# CircuitControlDriver.net
KiCad netlist of a schematic drawn in Altium Designer
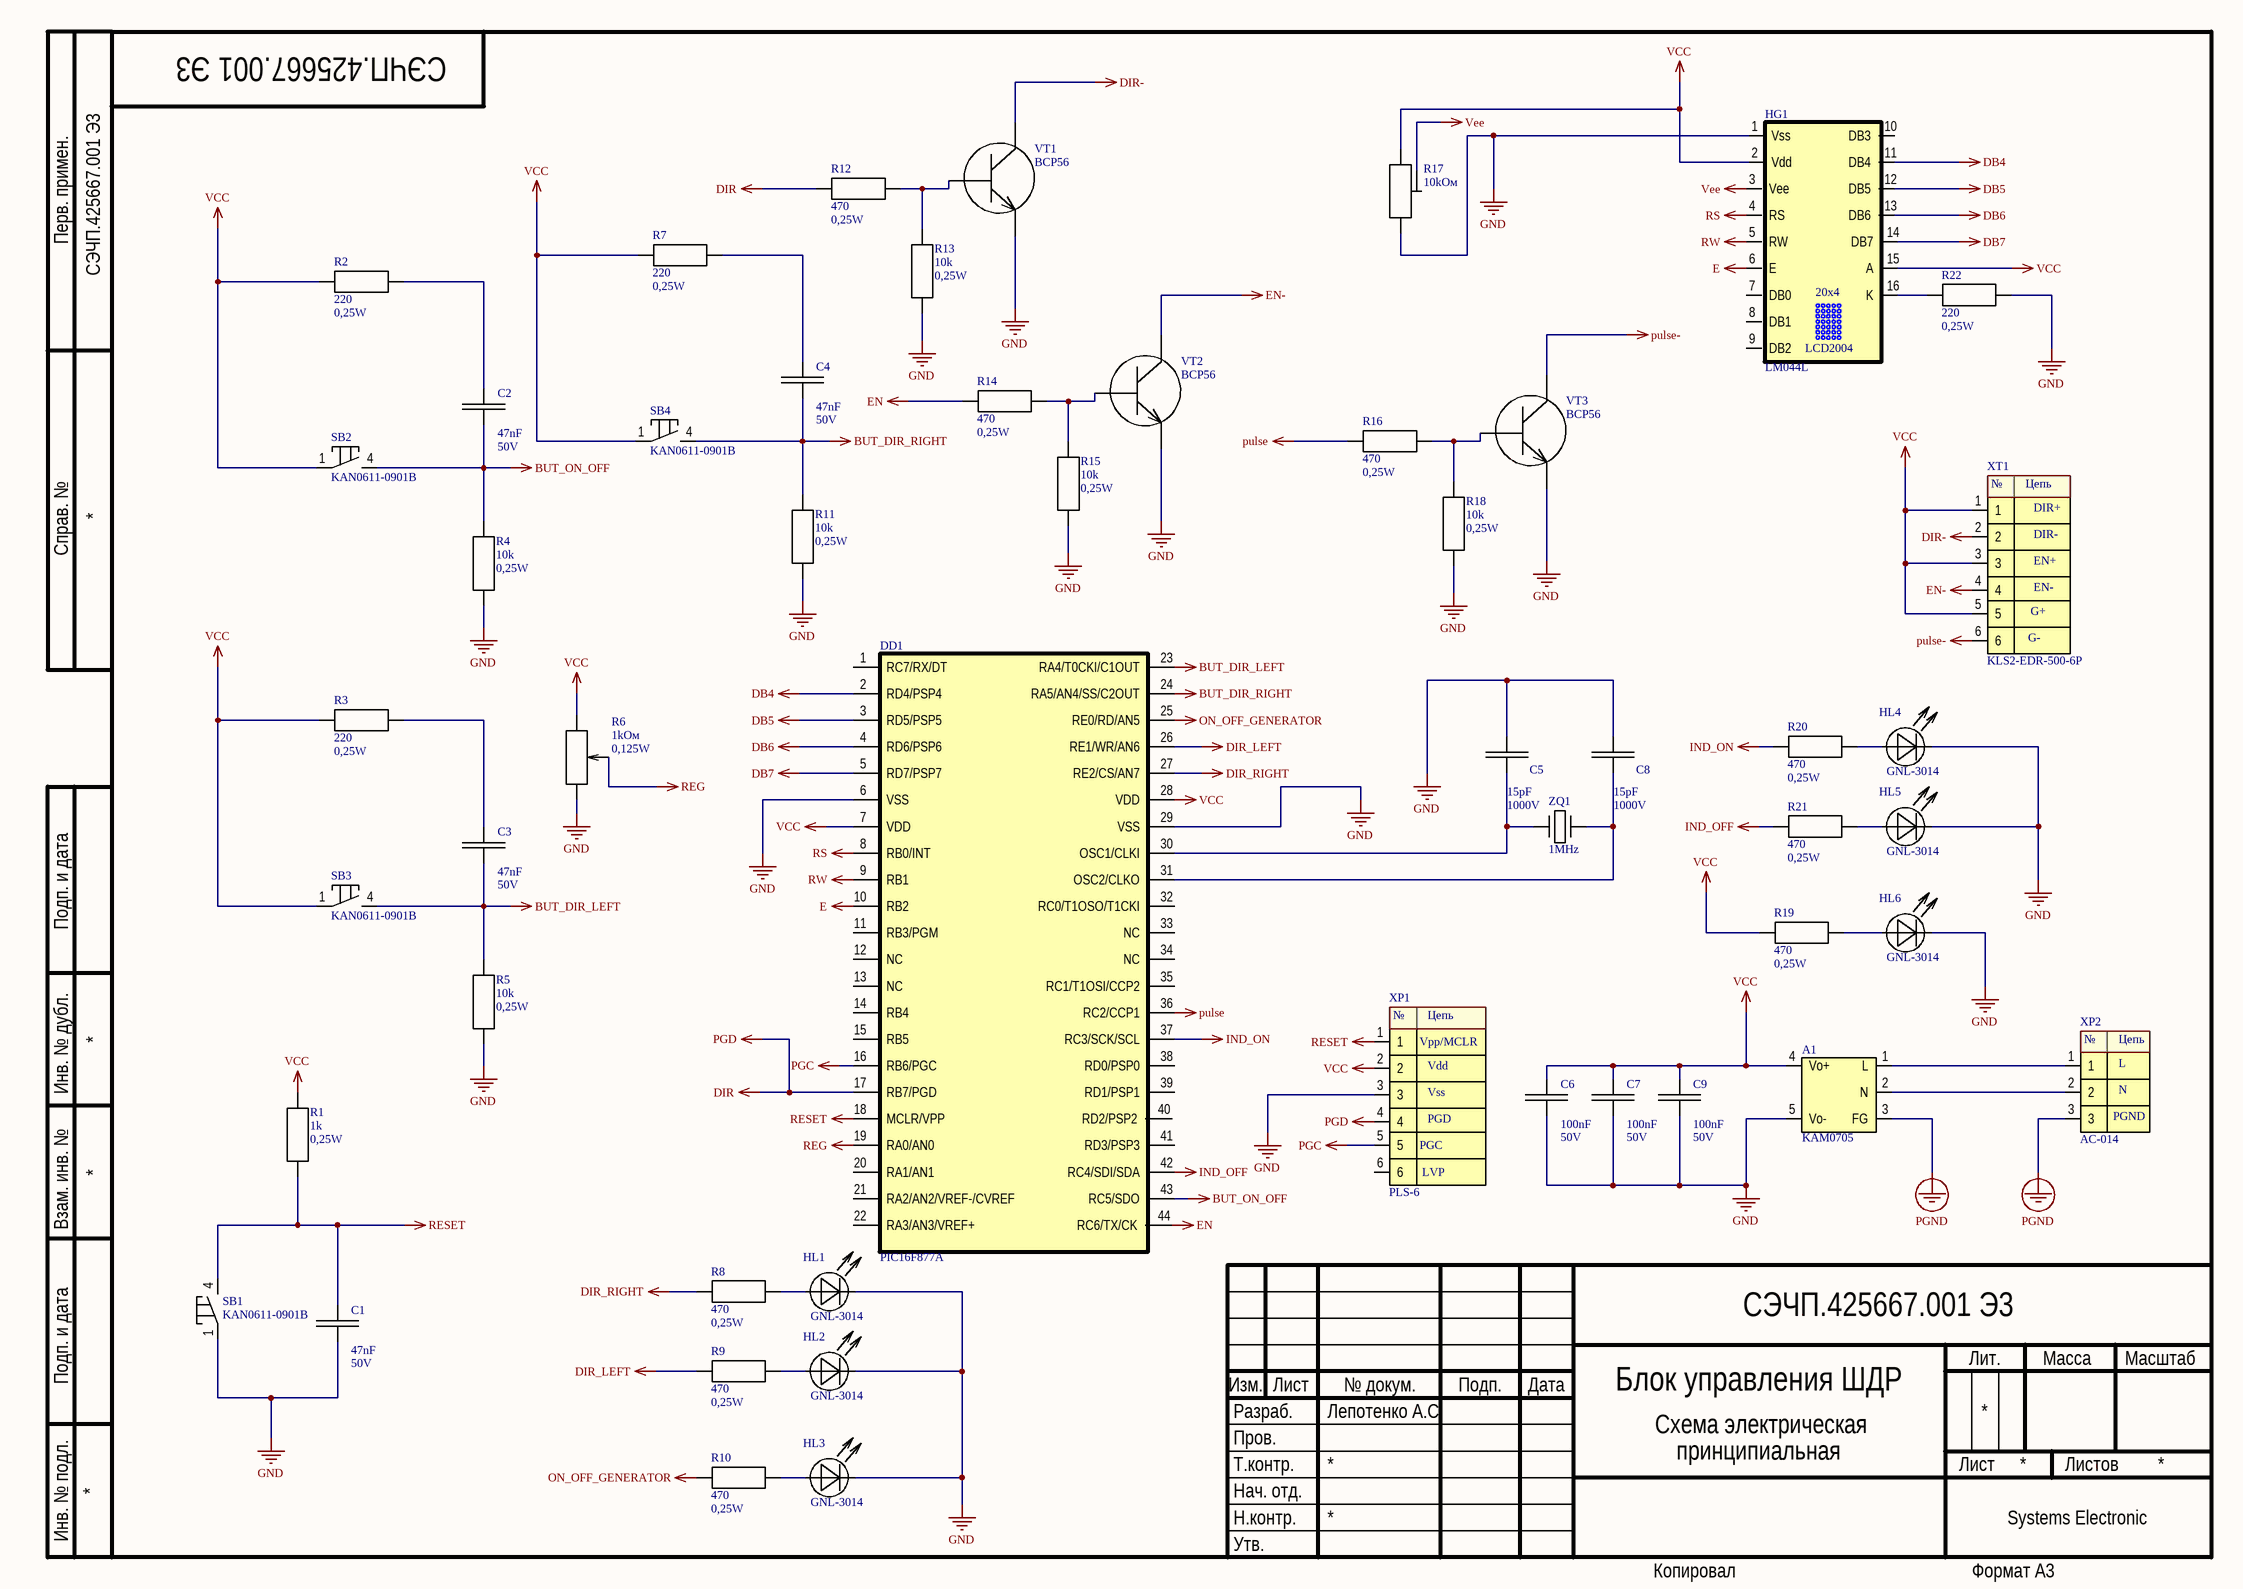
[diagram p0: CircuitControlDriver.SchDoc]

(export (version "E")
  (design (tool "Eeschema 10.0.6"))
  (components
    (comp (ref "A1")
      (value "KAM0705")
      (footprint "KAM705")
      (fields (field (name "MANUFACTURER") "CHINFA ELECTRONICS"))
      (libsource (lib "SchlibUGO") (part "KAM0705"))
    )
    (comp (ref "C1")
      (value "47nF")
      (footprint "CAP1206")
      (fields
        (field (name "VOLTAGE") "50V")
        (field (name "PART NUMBER") "120647nY5V-50V")
        (field (name "MANUFACTURER") "FAITHFULL LINK")
      )
      (libsource (lib "SchlibUGO") (part "Capasitor"))
    )
    (comp (ref "C2")
      (value "47nF")
      (footprint "CAP1206")
      (fields
        (field (name "VOLTAGE") "50V")
        (field (name "PART NUMBER") "120647nY5V-50V")
        (field (name "MANUFACTURER") "FAITHFULL LINK")
      )
      (libsource (lib "SchlibUGO") (part "Capasitor"))
    )
    (comp (ref "C3")
      (value "47nF")
      (footprint "CAP1206")
      (fields
        (field (name "VOLTAGE") "50V")
        (field (name "PART NUMBER") "120647nY5V-50V")
        (field (name "MANUFACTURER") "FAITHFULL LINK")
      )
      (libsource (lib "SchlibUGO") (part "Capasitor"))
    )
    (comp (ref "C4")
      (value "47nF")
      (footprint "CAP1206")
      (fields
        (field (name "VOLTAGE") "50V")
        (field (name "PART NUMBER") "120647nY5V-50V")
        (field (name "MANUFACTURER") "FAITHFULL LINK")
      )
      (libsource (lib "SchlibUGO") (part "Capasitor"))
    )
    (comp (ref "C5")
      (value "15pF")
      (footprint "CAP1206")
      (fields
        (field (name "VOLTAGE") "1000V")
        (field (name "PART NUMBER") "1206150NPO")
        (field (name "MANUFACTURER") "NPO")
      )
      (libsource (lib "SchlibUGO") (part "Capasitor"))
    )
    (comp (ref "C6")
      (value "100nF")
      (footprint "CAP1206")
      (fields
        (field (name "VOLTAGE") "50V")
        (field (name "PART NUMBER") "CL31B104KBCNNNC")
        (field (name "MANUFACTURER") "Samsung")
      )
      (libsource (lib "SchlibUGO") (part "Capasitor"))
    )
    (comp (ref "C7")
      (value "100nF")
      (footprint "CAP1206")
      (fields
        (field (name "VOLTAGE") "50V")
        (field (name "PART NUMBER") "CL31B104KBCNNNC")
        (field (name "MANUFACTURER") "Samsung")
      )
      (libsource (lib "SchlibUGO") (part "Capasitor"))
    )
    (comp (ref "C8")
      (value "15pF")
      (footprint "CAP1206")
      (fields
        (field (name "VOLTAGE") "1000V")
        (field (name "PART NUMBER") "1206150NPO")
        (field (name "MANUFACTURER") "NPO")
      )
      (libsource (lib "SchlibUGO") (part "Capasitor"))
    )
    (comp (ref "C9")
      (value "100nF")
      (footprint "CAP1206")
      (fields
        (field (name "VOLTAGE") "50V")
        (field (name "PART NUMBER") "CL31B104KBCNNNC")
        (field (name "MANUFACTURER") "Samsung")
      )
      (libsource (lib "SchlibUGO") (part "Capasitor"))
    )
    (comp (ref "DD1")
      (value "PIC16F877A")
      (footprint "TQFP80P1200X1200X120-44N")
      (fields (field (name "MANUFACTURER") "Micchip"))
      (libsource (lib "SchlibUGO") (part "PIC16F877A"))
    )
    (comp (ref "HG1")
      (value "LM044L")
      (footprint "LCD2004")
      (fields (field (name "PART NUMBER") "LM044L-HD44780U") (field (name "MANUFACTURER") "HITACHI"))
      (libsource (lib "SchlibUGO") (part "LM044L"))
    )
    (comp (ref "HL1")
      (value "GNL-3014")
      (footprint "GNL-3014")
      (fields (field (name "PART NUMBER") "GNL-3014SRD") (field (name "MANUFACTURER") "G-NOR"))
      (libsource (lib "SchlibUGO") (part "LED"))
    )
    (comp (ref "HL2")
      (value "GNL-3014")
      (footprint "GNL-3014")
      (fields (field (name "PART NUMBER") "GNL-3014SRD") (field (name "MANUFACTURER") "G-NOR"))
      (libsource (lib "SchlibUGO") (part "LED"))
    )
    (comp (ref "HL3")
      (value "GNL-3014")
      (footprint "GNL-3014")
      (fields (field (name "PART NUMBER") "GNL-3014SRD") (field (name "MANUFACTURER") "G-NOR"))
      (libsource (lib "SchlibUGO") (part "LED"))
    )
    (comp (ref "HL4")
      (value "GNL-3014")
      (footprint "GNL-3014")
      (fields (field (name "PART NUMBER") "GNL-3014SRD") (field (name "MANUFACTURER") "G-NOR"))
      (libsource (lib "SchlibUGO") (part "LED"))
    )
    (comp (ref "HL5")
      (value "GNL-3014")
      (footprint "GNL-3014")
      (fields (field (name "PART NUMBER") "GNL-3014SRD") (field (name "MANUFACTURER") "G-NOR"))
      (libsource (lib "SchlibUGO") (part "LED"))
    )
    (comp (ref "HL6")
      (value "GNL-3014")
      (footprint "GNL-3014")
      (fields (field (name "PART NUMBER") "GNL-3014SRD") (field (name "MANUFACTURER") "G-NOR"))
      (libsource (lib "SchlibUGO") (part "LED"))
    )
    (comp (ref "R1")
      (value "1k")
      (footprint "1206")
      (fields
        (field (name "MANUFACTURER") "Royal Ohm")
        (field (name "PART NUMBER") "RC1206FR-071KL")
        (field (name "POWER") "0,25W")
        (field (name "Comment") "10k")
      )
      (libsource (lib "SchlibUGO") (part "Resistor"))
    )
    (comp (ref "R2")
      (value "220")
      (footprint "1206")
      (fields
        (field (name "MANUFACTURER") "YAGEO")
        (field (name "PART NUMBER") "RC1206JR-07220L")
        (field (name "POWER") "0,25W")
      )
      (libsource (lib "SchlibUGO") (part "Resistor"))
    )
    (comp (ref "R3")
      (value "220")
      (footprint "1206")
      (fields
        (field (name "MANUFACTURER") "YAGEO")
        (field (name "PART NUMBER") "RC1206JR-07220L")
        (field (name "POWER") "0,25W")
      )
      (libsource (lib "SchlibUGO") (part "Resistor"))
    )
    (comp (ref "R4")
      (value "10k")
      (footprint "1206")
      (fields
        (field (name "MANUFACTURER") "YAGEO")
        (field (name "PART NUMBER") "RC1206JR-0710KL")
        (field (name "POWER") "0,25W")
      )
      (libsource (lib "SchlibUGO") (part "Resistor"))
    )
    (comp (ref "R5")
      (value "10k")
      (footprint "1206")
      (fields
        (field (name "MANUFACTURER") "YAGEO")
        (field (name "PART NUMBER") "RC1206JR-0710KL")
        (field (name "POWER") "0,25W")
      )
      (libsource (lib "SchlibUGO") (part "Resistor"))
    )
    (comp (ref "R6")
      (value "1kОм")
      (footprint "KC/C 16K1")
      (fields
        (field (name "PART NUMBER") "16K1")
        (field (name "MANUFACTURER") "RUICHI")
        (field (name "POWER") "0,125W")
      )
      (libsource (lib "SchlibUGO") (part "POT-HG"))
    )
    (comp (ref "R7")
      (value "220")
      (footprint "1206")
      (fields
        (field (name "MANUFACTURER") "YAGEO")
        (field (name "PART NUMBER") "RC1206JR-07220L")
        (field (name "POWER") "0,25W")
      )
      (libsource (lib "SchlibUGO") (part "Resistor"))
    )
    (comp (ref "R8")
      (value "470")
      (footprint "1206")
      (fields
        (field (name "MANUFACTURER") "YAGEO")
        (field (name "PART NUMBER") "RC1206JR-07470RL")
        (field (name "POWER") "0,25W")
      )
      (libsource (lib "SchlibUGO") (part "Resistor"))
    )
    (comp (ref "R9")
      (value "470")
      (footprint "1206")
      (fields
        (field (name "MANUFACTURER") "YAGEO")
        (field (name "PART NUMBER") "RC1206JR-07470RL")
        (field (name "POWER") "0,25W")
      )
      (libsource (lib "SchlibUGO") (part "Resistor"))
    )
    (comp (ref "R10")
      (value "470")
      (footprint "1206")
      (fields
        (field (name "MANUFACTURER") "YAGEO")
        (field (name "PART NUMBER") "RC1206JR-07470RL")
        (field (name "POWER") "0,25W")
      )
      (libsource (lib "SchlibUGO") (part "Resistor"))
    )
    (comp (ref "R11")
      (value "10k")
      (footprint "1206")
      (fields
        (field (name "MANUFACTURER") "YAGEO")
        (field (name "PART NUMBER") "RC1206JR-0710KL")
        (field (name "POWER") "0,25W")
      )
      (libsource (lib "SchlibUGO") (part "Resistor"))
    )
    (comp (ref "R12")
      (value "470")
      (footprint "1206")
      (fields
        (field (name "MANUFACTURER") "YAGEO")
        (field (name "PART NUMBER") "RC1206JR-07470RL")
        (field (name "POWER") "0,25W")
      )
      (libsource (lib "SchlibUGO") (part "Resistor"))
    )
    (comp (ref "R13")
      (value "10k")
      (footprint "1206")
      (fields
        (field (name "MANUFACTURER") "YAGEO")
        (field (name "PART NUMBER") "RC1206JR-0710KL")
        (field (name "POWER") "0,25W")
      )
      (libsource (lib "SchlibUGO") (part "Resistor"))
    )
    (comp (ref "R14")
      (value "470")
      (footprint "1206")
      (fields
        (field (name "MANUFACTURER") "YAGEO")
        (field (name "PART NUMBER") "RC1206JR-07470RL")
        (field (name "POWER") "0,25W")
      )
      (libsource (lib "SchlibUGO") (part "Resistor"))
    )
    (comp (ref "R15")
      (value "10k")
      (footprint "1206")
      (fields
        (field (name "MANUFACTURER") "YAGEO")
        (field (name "PART NUMBER") "RC1206JR-0710KL")
        (field (name "POWER") "0,25W")
      )
      (libsource (lib "SchlibUGO") (part "Resistor"))
    )
    (comp (ref "R16")
      (value "470")
      (footprint "1206")
      (fields
        (field (name "MANUFACTURER") "YAGEO")
        (field (name "PART NUMBER") "RC1206JR-07470RL")
        (field (name "POWER") "0,25W")
      )
      (libsource (lib "SchlibUGO") (part "Resistor"))
    )
    (comp (ref "R17")
      (value "10kОм")
      (footprint "3006P")
      (fields
        (field (name "PART NUMBER") "3006-103-Z-LF")
        (field (name "MANUFACTURER") "Bours")
        (field (name "POWER") "0,125W")
      )
      (libsource (lib "SchlibUGO") (part "POT"))
    )
    (comp (ref "R18")
      (value "10k")
      (footprint "1206")
      (fields
        (field (name "MANUFACTURER") "YAGEO")
        (field (name "PART NUMBER") "RC1206JR-0710KL")
        (field (name "POWER") "0,25W")
      )
      (libsource (lib "SchlibUGO") (part "Resistor"))
    )
    (comp (ref "R19")
      (value "470")
      (footprint "1206")
      (fields
        (field (name "MANUFACTURER") "YAGEO")
        (field (name "PART NUMBER") "RC1206JR-07470RL")
        (field (name "POWER") "0,25W")
      )
      (libsource (lib "SchlibUGO") (part "Resistor"))
    )
    (comp (ref "R20")
      (value "470")
      (footprint "1206")
      (fields
        (field (name "MANUFACTURER") "YAGEO")
        (field (name "PART NUMBER") "RC1206JR-07470RL")
        (field (name "POWER") "0,25W")
      )
      (libsource (lib "SchlibUGO") (part "Resistor"))
    )
    (comp (ref "R21")
      (value "470")
      (footprint "1206")
      (fields
        (field (name "MANUFACTURER") "YAGEO")
        (field (name "PART NUMBER") "RC1206JR-07470RL")
        (field (name "POWER") "0,25W")
      )
      (libsource (lib "SchlibUGO") (part "Resistor"))
    )
    (comp (ref "R22")
      (value "220")
      (footprint "1206")
      (fields
        (field (name "MANUFACTURER") "YAGEO")
        (field (name "PART NUMBER") "RC1206JR-07220L")
        (field (name "POWER") "0,25W")
      )
      (libsource (lib "SchlibUGO") (part "Resistor"))
    )
    (comp (ref "SB1")
      (value "KAN0611-0901B")
      (footprint "KLS2")
      (fields (field (name "MANUFACTURER") "RUICHI"))
      (libsource (lib "SchlibUGO") (part "Button"))
    )
    (comp (ref "SB2")
      (value "KAN0611-0901B")
      (footprint "KLS2")
      (fields (field (name "MANUFACTURER") "RUICHI"))
      (libsource (lib "SchlibUGO") (part "Button"))
    )
    (comp (ref "SB3")
      (value "KAN0611-0901B")
      (footprint "KLS2")
      (fields (field (name "MANUFACTURER") "RUICHI"))
      (libsource (lib "SchlibUGO") (part "Button"))
    )
    (comp (ref "SB4")
      (value "KAN0611-0901B")
      (footprint "KLS2")
      (fields (field (name "MANUFACTURER") "RUICHI"))
      (libsource (lib "SchlibUGO") (part "Button"))
    )
    (comp (ref "VT1")
      (value "BCP56")
      (footprint "SOT223")
      (fields (field (name "PART NUMBER") "BCP56-16") (field (name "MANUFACTURER") "NXP Semiconductors"))
      (libsource (lib "SchlibUGO") (part "BCP56-16"))
    )
    (comp (ref "VT2")
      (value "BCP56")
      (footprint "SOT223")
      (fields (field (name "PART NUMBER") "BCP56-16") (field (name "MANUFACTURER") "NXP Semiconductors"))
      (libsource (lib "SchlibUGO") (part "BCP56-16"))
    )
    (comp (ref "VT3")
      (value "BCP56")
      (footprint "SOT223")
      (fields (field (name "PART NUMBER") "BCP56-16") (field (name "MANUFACTURER") "NXP Semiconductors"))
      (libsource (lib "SchlibUGO") (part "BCP56-16"))
    )
    (comp (ref "XP1")
      (value "PLS-6")
      (footprint "DS1021-6")
      (fields (field (name "PART NUMBER") "PLS-40") (field (name "MANUFACTURER") "RUICHI"))
      (libsource (lib "SchlibUGO") (part "PLS-6-1"))
    )
    (comp (ref "XP2")
      (value "AC-014")
      (footprint "Power AC-014")
      (fields (field (name "MANUFACTURER") "RUICHI"))
      (libsource (lib "SchlibUGO") (part "Power Connector AC-014"))
    )
    (comp (ref "XT1")
      (value "KLS2-EDR-500-6P")
      (footprint "KLS2-EDR-500-6P")
      (fields (field (name "MANUFACTURER") "KLS"))
      (libsource (lib "SchlibUGO") (part "KLS2-EDR-500-6P"))
    )
    (comp (ref "ZQ1")
      (value "1MHz")
      (footprint "HC-51U")
      (fields (field (name "PART NUMBER") "HC-51") (field (name "MANUFACTURER") "CHina"))
      (libsource (lib "SchlibUGO") (part "Rzanator"))
    )
  )
  (nets
    (net (code "1") (name "BUT_DIR_LEFT") (class "Default")
      (node (ref "C3") (pin "2") (pinfunction "2_2") (pintype "passive"))
      (node (ref "DD1") (pin "23") (pinfunction "RA4/T0CKI/C1OUT_23") (pintype "passive"))
      (node (ref "R5") (pin "1") (pinfunction "1_1") (pintype "passive"))
      (node (ref "SB3") (pin "4") (pinfunction "4_4") (pintype "passive"))
    )
    (net (code "2") (name "BUT_DIR_RIGHT") (class "Default")
      (node (ref "C4") (pin "2") (pinfunction "2_2") (pintype "passive"))
      (node (ref "DD1") (pin "24") (pinfunction "RA5/AN4/SS/C2OUT_24") (pintype "passive"))
      (node (ref "R11") (pin "1") (pinfunction "1_1") (pintype "passive"))
      (node (ref "SB4") (pin "4") (pinfunction "4_4") (pintype "passive"))
    )
    (net (code "3") (name "BUT_ON_OFF") (class "Default")
      (node (ref "C2") (pin "2") (pinfunction "2_2") (pintype "passive"))
      (node (ref "DD1") (pin "43") (pinfunction "RC5/SDO_43") (pintype "passive"))
      (node (ref "R4") (pin "1") (pinfunction "1_1") (pintype "passive"))
      (node (ref "SB2") (pin "4") (pinfunction "4_4") (pintype "passive"))
    )
    (net (code "4") (name "DB4") (class "Default")
      (node (ref "DD1") (pin "2") (pinfunction "RD4/PSP4_2") (pintype "passive"))
      (node (ref "HG1") (pin "11") (pinfunction "DB4_11") (pintype "passive"))
    )
    (net (code "5") (name "DB5") (class "Default")
      (node (ref "DD1") (pin "3") (pinfunction "RD5/PSP5_3") (pintype "passive"))
      (node (ref "HG1") (pin "12") (pinfunction "DB5_12") (pintype "passive"))
    )
    (net (code "6") (name "DB6") (class "Default")
      (node (ref "DD1") (pin "4") (pinfunction "RD6/PSP6_4") (pintype "passive"))
      (node (ref "HG1") (pin "13") (pinfunction "DB6_13") (pintype "passive"))
    )
    (net (code "7") (name "DB7") (class "Default")
      (node (ref "DD1") (pin "5") (pinfunction "RD7/PSP7_5") (pintype "passive"))
      (node (ref "HG1") (pin "14") (pinfunction "DB7_14") (pintype "passive"))
    )
    (net (code "8") (name "DIR") (class "Default")
      (node (ref "DD1") (pin "17") (pinfunction "RB7/PGD_17") (pintype "passive"))
      (node (ref "R12") (pin "1") (pinfunction "1_1") (pintype "passive"))
      (node (ref "XP1") (pin "4") (pinfunction "4_4") (pintype "passive"))
    )
    (net (code "9") (name "DIR-") (class "Default")
      (node (ref "VT1") (pin "2") (pinfunction "2_2") (pintype "passive"))
      (node (ref "XT1") (pin "2") (pinfunction "2_2") (pintype "passive"))
    )
    (net (code "10") (name "DIR_LEFT") (class "Default")
      (node (ref "DD1") (pin "26") (pinfunction "RE1/WR/AN6_26") (pintype "passive"))
      (node (ref "R9") (pin "1") (pinfunction "1_1") (pintype "passive"))
    )
    (net (code "11") (name "DIR_RIGHT") (class "Default")
      (node (ref "DD1") (pin "27") (pinfunction "RE2/CS/AN7_27") (pintype "passive"))
      (node (ref "R8") (pin "1") (pinfunction "1_1") (pintype "passive"))
    )
    (net (code "12") (name "E") (class "Default")
      (node (ref "DD1") (pin "10") (pinfunction "RB2_10") (pintype "passive"))
      (node (ref "HG1") (pin "6") (pinfunction "E_6") (pintype "passive"))
    )
    (net (code "13") (name "EN") (class "Default")
      (node (ref "DD1") (pin "44") (pinfunction "RC6/TX/CK_44") (pintype "passive"))
      (node (ref "R14") (pin "1") (pinfunction "1_1") (pintype "passive"))
    )
    (net (code "14") (name "EN-") (class "Default")
      (node (ref "VT2") (pin "2") (pinfunction "2_2") (pintype "passive"))
      (node (ref "XT1") (pin "4") (pinfunction "4_4") (pintype "passive"))
    )
    (net (code "15") (name "GND") (class "Default")
      (node (ref "A1") (pin "5") (pinfunction "Vo-_5") (pintype "passive"))
      (node (ref "C1") (pin "2") (pinfunction "2_2") (pintype "passive"))
      (node (ref "C5") (pin "1") (pinfunction "1_1") (pintype "passive"))
      (node (ref "C6") (pin "2") (pinfunction "2_2") (pintype "passive"))
      (node (ref "C7") (pin "2") (pinfunction "2_2") (pintype "passive"))
      (node (ref "C8") (pin "1") (pinfunction "1_1") (pintype "passive"))
      (node (ref "C9") (pin "2") (pinfunction "2_2") (pintype "passive"))
      (node (ref "DD1") (pin "29") (pinfunction "VSS_29") (pintype "passive"))
      (node (ref "DD1") (pin "6") (pinfunction "VSS_6") (pintype "passive"))
      (node (ref "HG1") (pin "1") (pinfunction "Vss_1") (pintype "passive"))
      (node (ref "HL1") (pin "2") (pinfunction "2_2") (pintype "passive"))
      (node (ref "HL2") (pin "2") (pinfunction "2_2") (pintype "passive"))
      (node (ref "HL3") (pin "2") (pinfunction "2_2") (pintype "passive"))
      (node (ref "HL4") (pin "2") (pinfunction "2_2") (pintype "passive"))
      (node (ref "HL5") (pin "2") (pinfunction "2_2") (pintype "passive"))
      (node (ref "HL6") (pin "2") (pinfunction "2_2") (pintype "passive"))
      (node (ref "R11") (pin "2") (pinfunction "2_2") (pintype "passive"))
      (node (ref "R13") (pin "2") (pinfunction "2_2") (pintype "passive"))
      (node (ref "R15") (pin "2") (pinfunction "2_2") (pintype "passive"))
      (node (ref "R17") (pin "1") (pinfunction "1_1") (pintype "passive"))
      (node (ref "R18") (pin "2") (pinfunction "2_2") (pintype "passive"))
      (node (ref "R22") (pin "1") (pinfunction "1_1") (pintype "passive"))
      (node (ref "R4") (pin "2") (pinfunction "2_2") (pintype "passive"))
      (node (ref "R5") (pin "2") (pinfunction "2_2") (pintype "passive"))
      (node (ref "R6") (pin "3") (pinfunction "3_3") (pintype "passive"))
      (node (ref "SB1") (pin "1") (pinfunction "1_1") (pintype "passive"))
      (node (ref "VT1") (pin "3") (pinfunction "3_3") (pintype "passive"))
      (node (ref "VT2") (pin "3") (pinfunction "3_3") (pintype "passive"))
      (node (ref "VT3") (pin "3") (pinfunction "3_3") (pintype "passive"))
      (node (ref "XP1") (pin "3") (pinfunction "3_3") (pintype "passive"))
    )
    (net (code "16") (name "IND_OFF") (class "Default")
      (node (ref "DD1") (pin "42") (pinfunction "RC4/SDI/SDA_42") (pintype "passive"))
      (node (ref "R21") (pin "1") (pinfunction "1_1") (pintype "passive"))
    )
    (net (code "17") (name "IND_ON") (class "Default")
      (node (ref "DD1") (pin "37") (pinfunction "RC3/SCK/SCL_37") (pintype "passive"))
      (node (ref "R20") (pin "1") (pinfunction "1_1") (pintype "passive"))
    )
    (net (code "18") (name "Net-(A1-L)") (class "Default")
      (node (ref "A1") (pin "1") (pinfunction "L_1") (pintype "passive"))
      (node (ref "XP2") (pin "1") (pinfunction "1_1") (pintype "passive"))
    )
    (net (code "19") (name "Net-(A1-N)") (class "Default")
      (node (ref "A1") (pin "2") (pinfunction "N_2") (pintype "passive"))
      (node (ref "XP2") (pin "2") (pinfunction "2_2") (pintype "passive"))
    )
    (net (code "20") (name "Net-(C2-Pad1)") (class "Default")
      (node (ref "C2") (pin "1") (pinfunction "1_1") (pintype "passive"))
      (node (ref "R2") (pin "1") (pinfunction "1_1") (pintype "passive"))
    )
    (net (code "21") (name "Net-(C3-Pad1)") (class "Default")
      (node (ref "C3") (pin "1") (pinfunction "1_1") (pintype "passive"))
      (node (ref "R3") (pin "1") (pinfunction "1_1") (pintype "passive"))
    )
    (net (code "22") (name "Net-(C4-Pad1)") (class "Default")
      (node (ref "C4") (pin "1") (pinfunction "1_1") (pintype "passive"))
      (node (ref "R7") (pin "1") (pinfunction "1_1") (pintype "passive"))
    )
    (net (code "23") (name "Net-(DD1-OSC1{slash}CLKI)") (class "Default")
      (node (ref "C5") (pin "2") (pinfunction "2_2") (pintype "passive"))
      (node (ref "DD1") (pin "30") (pinfunction "OSC1/CLKI_30") (pintype "passive"))
      (node (ref "ZQ1") (pin "1") (pinfunction "1_1") (pintype "passive"))
    )
    (net (code "24") (name "Net-(DD1-OSC2{slash}CLKO)") (class "Default")
      (node (ref "C8") (pin "2") (pinfunction "2_2") (pintype "passive"))
      (node (ref "DD1") (pin "31") (pinfunction "OSC2/CLKO_31") (pintype "passive"))
      (node (ref "ZQ1") (pin "2") (pinfunction "2_2") (pintype "passive"))
    )
    (net (code "25") (name "Net-(HG1-K)") (class "Default")
      (node (ref "HG1") (pin "16") (pinfunction "K_16") (pintype "passive"))
      (node (ref "R22") (pin "2") (pinfunction "2_2") (pintype "passive"))
    )
    (net (code "26") (name "Net-(HL1-Pad1)") (class "Default")
      (node (ref "HL1") (pin "1") (pinfunction "1_1") (pintype "passive"))
      (node (ref "R8") (pin "2") (pinfunction "2_2") (pintype "passive"))
    )
    (net (code "27") (name "Net-(HL2-Pad1)") (class "Default")
      (node (ref "HL2") (pin "1") (pinfunction "1_1") (pintype "passive"))
      (node (ref "R9") (pin "2") (pinfunction "2_2") (pintype "passive"))
    )
    (net (code "28") (name "Net-(HL3-Pad1)") (class "Default")
      (node (ref "HL3") (pin "1") (pinfunction "1_1") (pintype "passive"))
      (node (ref "R10") (pin "2") (pinfunction "2_2") (pintype "passive"))
    )
    (net (code "29") (name "Net-(HL4-Pad1)") (class "Default")
      (node (ref "HL4") (pin "1") (pinfunction "1_1") (pintype "passive"))
      (node (ref "R20") (pin "2") (pinfunction "2_2") (pintype "passive"))
    )
    (net (code "30") (name "Net-(HL5-Pad1)") (class "Default")
      (node (ref "HL5") (pin "1") (pinfunction "1_1") (pintype "passive"))
      (node (ref "R21") (pin "2") (pinfunction "2_2") (pintype "passive"))
    )
    (net (code "31") (name "Net-(HL6-Pad1)") (class "Default")
      (node (ref "HL6") (pin "1") (pinfunction "1_1") (pintype "passive"))
      (node (ref "R19") (pin "2") (pinfunction "2_2") (pintype "passive"))
    )
    (net (code "32") (name "Net-(R12-Pad2)") (class "Default")
      (node (ref "R12") (pin "2") (pinfunction "2_2") (pintype "passive"))
      (node (ref "R13") (pin "1") (pinfunction "1_1") (pintype "passive"))
      (node (ref "VT1") (pin "1") (pinfunction "1_1") (pintype "passive"))
    )
    (net (code "33") (name "Net-(R14-Pad2)") (class "Default")
      (node (ref "R14") (pin "2") (pinfunction "2_2") (pintype "passive"))
      (node (ref "R15") (pin "1") (pinfunction "1_1") (pintype "passive"))
      (node (ref "VT2") (pin "1") (pinfunction "1_1") (pintype "passive"))
    )
    (net (code "34") (name "Net-(R16-Pad2)") (class "Default")
      (node (ref "R16") (pin "2") (pinfunction "2_2") (pintype "passive"))
      (node (ref "R18") (pin "1") (pinfunction "1_1") (pintype "passive"))
      (node (ref "VT3") (pin "1") (pinfunction "1_1") (pintype "passive"))
    )
    (net (code "35") (name "ON_OFF_GENERATOR") (class "Default")
      (node (ref "DD1") (pin "25") (pinfunction "RE0/RD/AN5_25") (pintype "passive"))
      (node (ref "R10") (pin "1") (pinfunction "1_1") (pintype "passive"))
    )
    (net (code "36") (name "PGC") (class "Default")
      (node (ref "DD1") (pin "16") (pinfunction "RB6/PGC_16") (pintype "passive"))
      (node (ref "XP1") (pin "5") (pinfunction "5_5") (pintype "passive"))
    )
    (net (code "37") (name "PGND") (class "Default")
      (node (ref "A1") (pin "3") (pinfunction "FG_3") (pintype "passive"))
      (node (ref "XP2") (pin "3") (pinfunction "3_3") (pintype "passive"))
    )
    (net (code "38") (name "REG") (class "Default")
      (node (ref "DD1") (pin "19") (pinfunction "RA0/AN0_19") (pintype "passive"))
      (node (ref "R6") (pin "2") (pinfunction "2_2") (pintype "passive"))
    )
    (net (code "39") (name "RESET") (class "Default")
      (node (ref "C1") (pin "1") (pinfunction "1_1") (pintype "passive"))
      (node (ref "DD1") (pin "18") (pinfunction "MCLR/VPP_18") (pintype "passive"))
      (node (ref "R1") (pin "2") (pinfunction "2_2") (pintype "passive"))
      (node (ref "SB1") (pin "4") (pinfunction "4_4") (pintype "passive"))
      (node (ref "XP1") (pin "1") (pinfunction "1_1") (pintype "passive"))
    )
    (net (code "40") (name "RS") (class "Default")
      (node (ref "DD1") (pin "8") (pinfunction "RB0/INT_8") (pintype "passive"))
      (node (ref "HG1") (pin "4") (pinfunction "RS_4") (pintype "passive"))
    )
    (net (code "41") (name "RW") (class "Default")
      (node (ref "DD1") (pin "9") (pinfunction "RB1_9") (pintype "passive"))
      (node (ref "HG1") (pin "5") (pinfunction "RW_5") (pintype "passive"))
    )
    (net (code "42") (name "VCC") (class "Default")
      (node (ref "A1") (pin "4") (pinfunction "Vo+_4") (pintype "passive"))
      (node (ref "C6") (pin "1") (pinfunction "1_1") (pintype "passive"))
      (node (ref "C7") (pin "1") (pinfunction "1_1") (pintype "passive"))
      (node (ref "C9") (pin "1") (pinfunction "1_1") (pintype "passive"))
      (node (ref "DD1") (pin "28") (pinfunction "VDD_28") (pintype "passive"))
      (node (ref "DD1") (pin "7") (pinfunction "VDD_7") (pintype "passive"))
      (node (ref "HG1") (pin "15") (pinfunction "A_15") (pintype "passive"))
      (node (ref "HG1") (pin "2") (pinfunction "Vdd_2") (pintype "passive"))
      (node (ref "R1") (pin "1") (pinfunction "1_1") (pintype "passive"))
      (node (ref "R17") (pin "3") (pinfunction "3_3") (pintype "passive"))
      (node (ref "R19") (pin "1") (pinfunction "1_1") (pintype "passive"))
      (node (ref "R2") (pin "2") (pinfunction "2_2") (pintype "passive"))
      (node (ref "R3") (pin "2") (pinfunction "2_2") (pintype "passive"))
      (node (ref "R6") (pin "1") (pinfunction "1_1") (pintype "passive"))
      (node (ref "R7") (pin "2") (pinfunction "2_2") (pintype "passive"))
      (node (ref "SB2") (pin "1") (pinfunction "1_1") (pintype "passive"))
      (node (ref "SB3") (pin "1") (pinfunction "1_1") (pintype "passive"))
      (node (ref "SB4") (pin "1") (pinfunction "1_1") (pintype "passive"))
      (node (ref "XP1") (pin "2") (pinfunction "2_2") (pintype "passive"))
      (node (ref "XT1") (pin "1") (pinfunction "1_1") (pintype "passive"))
      (node (ref "XT1") (pin "3") (pinfunction "3_3") (pintype "passive"))
      (node (ref "XT1") (pin "5") (pinfunction "5_5") (pintype "passive"))
    )
    (net (code "43") (name "Vee") (class "Default")
      (node (ref "HG1") (pin "3") (pinfunction "Vee_3") (pintype "passive"))
      (node (ref "R17") (pin "2") (pinfunction "2_2") (pintype "passive"))
    )
    (net (code "44") (name "pulse") (class "Default")
      (node (ref "DD1") (pin "36") (pinfunction "RC2/CCP1_36") (pintype "passive"))
      (node (ref "R16") (pin "1") (pinfunction "1_1") (pintype "passive"))
    )
    (net (code "45") (name "pulse-") (class "Default")
      (node (ref "VT3") (pin "2") (pinfunction "2_2") (pintype "passive"))
      (node (ref "XT1") (pin "6") (pinfunction "6_6") (pintype "passive"))
    )
    (net (code "46") (name "unconnected-(DD1-NC-Pad12)") (class "Default")
      (node (ref "DD1") (pin "12") (pinfunction "NC_12") (pintype "passive"))
    )
    (net (code "47") (name "unconnected-(DD1-NC-Pad13)") (class "Default")
      (node (ref "DD1") (pin "13") (pinfunction "NC_13") (pintype "passive"))
    )
    (net (code "48") (name "unconnected-(DD1-NC-Pad33)") (class "Default")
      (node (ref "DD1") (pin "33") (pinfunction "NC_33") (pintype "passive"))
    )
    (net (code "49") (name "unconnected-(DD1-NC-Pad34)") (class "Default")
      (node (ref "DD1") (pin "34") (pinfunction "NC_34") (pintype "passive"))
    )
    (net (code "50") (name "unconnected-(DD1-RA1{slash}AN1-Pad20)") (class "Default")
      (node (ref "DD1") (pin "20") (pinfunction "RA1/AN1_20") (pintype "passive"))
    )
    (net (code "51") (name "unconnected-(DD1-RA2{slash}AN2{slash}VREF-{slash}CVREF-Pad21)") (class "Default")
      (node (ref "DD1") (pin "21") (pinfunction "RA2/AN2/VREF-/CVREF_21") (pintype "passive"))
    )
    (net (code "52") (name "unconnected-(DD1-RA3{slash}AN3{slash}VREF+-Pad22)") (class "Default")
      (node (ref "DD1") (pin "22") (pinfunction "RA3/AN3/VREF+_22") (pintype "passive"))
    )
    (net (code "53") (name "unconnected-(DD1-RB3{slash}PGM-Pad11)") (class "Default")
      (node (ref "DD1") (pin "11") (pinfunction "RB3/PGM_11") (pintype "passive"))
    )
    (net (code "54") (name "unconnected-(DD1-RB4-Pad14)") (class "Default")
      (node (ref "DD1") (pin "14") (pinfunction "RB4_14") (pintype "passive"))
    )
    (net (code "55") (name "unconnected-(DD1-RB5-Pad15)") (class "Default")
      (node (ref "DD1") (pin "15") (pinfunction "RB5_15") (pintype "passive"))
    )
    (net (code "56") (name "unconnected-(DD1-RC0{slash}T1OSO{slash}T1CKI-Pad32)") (class "Default")
      (node (ref "DD1") (pin "32") (pinfunction "RC0/T1OSO/T1CKI_32") (pintype "passive"))
    )
    (net (code "57") (name "unconnected-(DD1-RC1{slash}T1OSI{slash}CCP2-Pad35)") (class "Default")
      (node (ref "DD1") (pin "35") (pinfunction "RC1/T1OSI/CCP2_35") (pintype "passive"))
    )
    (net (code "58") (name "unconnected-(DD1-RC7{slash}RX{slash}DT-Pad1)") (class "Default")
      (node (ref "DD1") (pin "1") (pinfunction "RC7/RX/DT_1") (pintype "passive"))
    )
    (net (code "59") (name "unconnected-(DD1-RD0{slash}PSP0-Pad38)") (class "Default")
      (node (ref "DD1") (pin "38") (pinfunction "RD0/PSP0_38") (pintype "passive"))
    )
    (net (code "60") (name "unconnected-(DD1-RD1{slash}PSP1-Pad39)") (class "Default")
      (node (ref "DD1") (pin "39") (pinfunction "RD1/PSP1_39") (pintype "passive"))
    )
    (net (code "61") (name "unconnected-(DD1-RD2{slash}PSP2-Pad40)") (class "Default")
      (node (ref "DD1") (pin "40") (pinfunction "RD2/PSP2_40") (pintype "passive"))
    )
    (net (code "62") (name "unconnected-(DD1-RD3{slash}PSP3-Pad41)") (class "Default")
      (node (ref "DD1") (pin "41") (pinfunction "RD3/PSP3_41") (pintype "passive"))
    )
    (net (code "63") (name "unconnected-(HG1-DB0-Pad7)") (class "Default")
      (node (ref "HG1") (pin "7") (pinfunction "DB0_7") (pintype "passive"))
    )
    (net (code "64") (name "unconnected-(HG1-DB1-Pad8)") (class "Default")
      (node (ref "HG1") (pin "8") (pinfunction "DB1_8") (pintype "passive"))
    )
    (net (code "65") (name "unconnected-(HG1-DB2-Pad9)") (class "Default")
      (node (ref "HG1") (pin "9") (pinfunction "DB2_9") (pintype "passive"))
    )
    (net (code "66") (name "unconnected-(HG1-DB3-Pad10)") (class "Default")
      (node (ref "HG1") (pin "10") (pinfunction "DB3_10") (pintype "passive"))
    )
    (net (code "67") (name "unconnected-(XP1-Pad6)") (class "Default")
      (node (ref "XP1") (pin "6") (pinfunction "6_6") (pintype "passive"))
    )
  )
)
